# Slave.net
KiCad netlist of a schematic drawn in EAGLE
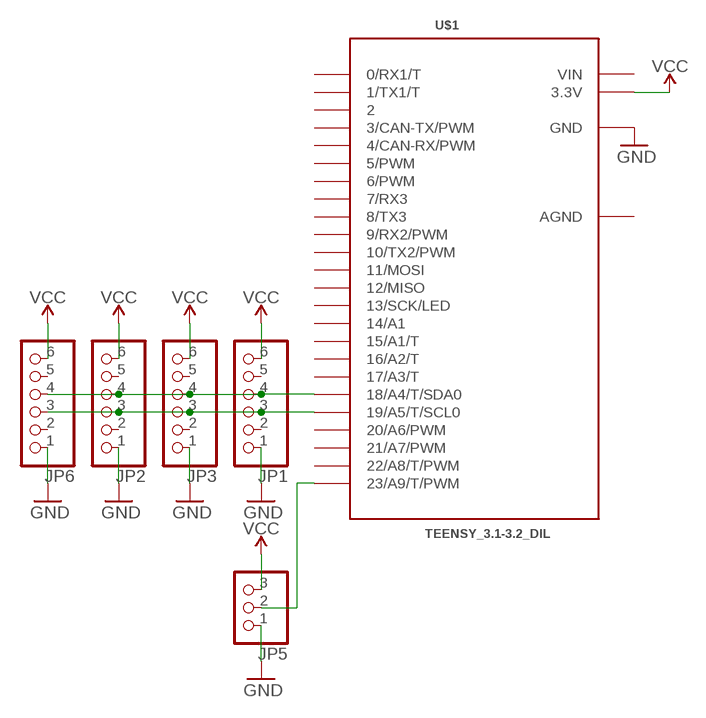
[diagram p0: schematic, sheet 1]

(export (version "E")
  (design (tool "Eeschema 10.0.6"))
  (components
    (comp (ref "JP1")
      (value "PINHD-1X6")
      (footprint "eagle-import:1X06")
      (libsource (lib "eagle-import") (part "PINHD-1X6"))
    )
    (comp (ref "JP2")
      (value "PINHD-1X6/90")
      (footprint "eagle-import:1X06_90")
      (libsource (lib "eagle-import") (part "PINHD-1X6/90"))
    )
    (comp (ref "JP3")
      (value "PINHD-1X6/90")
      (footprint "eagle-import:1X06_90")
      (libsource (lib "eagle-import") (part "PINHD-1X6/90"))
    )
    (comp (ref "JP5")
      (value "PINHD-1X3")
      (footprint "eagle-import:1X03")
      (libsource (lib "eagle-import") (part "PINHD-1X3"))
    )
    (comp (ref "JP6")
      (value "PINHD-1X6/90")
      (footprint "eagle-import:1X06_90")
      (libsource (lib "eagle-import") (part "PINHD-1X6/90"))
    )
    (comp (ref "U$1")
      (value "TEENSY_3.1-3.2_DIL")
      (footprint "eagle-import:TEENSY_3.0-3.2&LC_DIL")
      (libsource (lib "eagle-import") (part "TEENSY_3.1-3.2_DIL"))
    )
  )
  (nets
    (net (code "1") (name "/AGND") (class "Default")
      (node (ref "U$1") (pin "AGND") (pinfunction "AGND_AGND") (pintype "power_in"))
    )
    (net (code "2") (name "/VIN") (class "Default")
      (node (ref "U$1") (pin "VIN") (pinfunction "VIN_VIN") (pintype "power_in"))
    )
    (net (code "3") (name "GND") (class "Default")
      (node (ref "JP1") (pin "1") (pinfunction "1_1") (pintype "passive"))
      (node (ref "JP2") (pin "1") (pinfunction "1_1") (pintype "passive"))
      (node (ref "JP3") (pin "1") (pinfunction "1_1") (pintype "passive"))
      (node (ref "JP5") (pin "1") (pinfunction "1_1") (pintype "passive"))
      (node (ref "JP6") (pin "1") (pinfunction "1_1") (pintype "passive"))
      (node (ref "U$1") (pin "GND") (pinfunction "GND_GND") (pintype "power_in"))
    )
    (net (code "4") (name "Net-(U$1-18{slash}A4{slash}T{slash}SDA0)") (class "Default")
      (node (ref "JP1") (pin "4") (pinfunction "4_4") (pintype "passive"))
      (node (ref "JP2") (pin "4") (pinfunction "4_4") (pintype "passive"))
      (node (ref "JP3") (pin "4") (pinfunction "4_4") (pintype "passive"))
      (node (ref "JP6") (pin "4") (pinfunction "4_4") (pintype "passive"))
      (node (ref "U$1") (pin "18/A4") (pinfunction "18/A4/T/SDA0_18/A4") (pintype "bidirectional"))
    )
    (net (code "5") (name "Net-(U$1-19{slash}A5{slash}T{slash}SCL0)") (class "Default")
      (node (ref "JP1") (pin "3") (pinfunction "3_3") (pintype "passive"))
      (node (ref "JP2") (pin "3") (pinfunction "3_3") (pintype "passive"))
      (node (ref "JP3") (pin "3") (pinfunction "3_3") (pintype "passive"))
      (node (ref "JP6") (pin "3") (pinfunction "3_3") (pintype "passive"))
      (node (ref "U$1") (pin "19/A5") (pinfunction "19/A5/T/SCL0_19/A5") (pintype "bidirectional"))
    )
    (net (code "6") (name "Net-(U$1-23{slash}A9{slash}T{slash}PWM)") (class "Default")
      (node (ref "JP5") (pin "2") (pinfunction "2_2") (pintype "passive"))
      (node (ref "U$1") (pin "23/A9") (pinfunction "23/A9/T/PWM_23/A9") (pintype "bidirectional"))
    )
    (net (code "7") (name "VCC") (class "Default")
      (node (ref "JP1") (pin "6") (pinfunction "6_6") (pintype "passive"))
      (node (ref "JP2") (pin "6") (pinfunction "6_6") (pintype "passive"))
      (node (ref "JP3") (pin "6") (pinfunction "6_6") (pintype "passive"))
      (node (ref "JP5") (pin "3") (pinfunction "3_3") (pintype "passive"))
      (node (ref "JP6") (pin "6") (pinfunction "6_6") (pintype "passive"))
      (node (ref "U$1") (pin "3.3V") (pinfunction "3.3V_3.3V") (pintype "power_in"))
    )
    (net (code "8") (name "unconnected-(JP1-Pad2)") (class "Default")
      (node (ref "JP1") (pin "2") (pinfunction "2_2") (pintype "passive"))
    )
    (net (code "9") (name "unconnected-(JP1-Pad5)") (class "Default")
      (node (ref "JP1") (pin "5") (pinfunction "5_5") (pintype "passive"))
    )
    (net (code "10") (name "unconnected-(JP2-Pad2)") (class "Default")
      (node (ref "JP2") (pin "2") (pinfunction "2_2") (pintype "passive"))
    )
    (net (code "11") (name "unconnected-(JP2-Pad5)") (class "Default")
      (node (ref "JP2") (pin "5") (pinfunction "5_5") (pintype "passive"))
    )
    (net (code "12") (name "unconnected-(JP3-Pad2)") (class "Default")
      (node (ref "JP3") (pin "2") (pinfunction "2_2") (pintype "passive"))
    )
    (net (code "13") (name "unconnected-(JP3-Pad5)") (class "Default")
      (node (ref "JP3") (pin "5") (pinfunction "5_5") (pintype "passive"))
    )
    (net (code "14") (name "unconnected-(JP6-Pad2)") (class "Default")
      (node (ref "JP6") (pin "2") (pinfunction "2_2") (pintype "passive"))
    )
    (net (code "15") (name "unconnected-(JP6-Pad5)") (class "Default")
      (node (ref "JP6") (pin "5") (pinfunction "5_5") (pintype "passive"))
    )
    (net (code "16") (name "unconnected-(U$1-0{slash}RX1{slash}T-Pad0)") (class "Default")
      (node (ref "U$1") (pin "0") (pinfunction "0/RX1/T_0") (pintype "bidirectional"))
    )
    (net (code "17") (name "unconnected-(U$1-1{slash}TX1{slash}T-Pad1)") (class "Default")
      (node (ref "U$1") (pin "1") (pinfunction "1/TX1/T_1") (pintype "bidirectional"))
    )
    (net (code "18") (name "unconnected-(U$1-3{slash}CAN-TX{slash}PWM-Pad3)") (class "Default")
      (node (ref "U$1") (pin "3") (pinfunction "3/CAN-TX/PWM_3") (pintype "bidirectional"))
    )
    (net (code "19") (name "unconnected-(U$1-4{slash}CAN-RX{slash}PWM-Pad4)") (class "Default")
      (node (ref "U$1") (pin "4") (pinfunction "4/CAN-RX/PWM_4") (pintype "bidirectional"))
    )
    (net (code "20") (name "unconnected-(U$1-5{slash}PWM-Pad5)") (class "Default")
      (node (ref "U$1") (pin "5") (pinfunction "5/PWM_5") (pintype "bidirectional"))
    )
    (net (code "21") (name "unconnected-(U$1-6{slash}PWM-Pad6)") (class "Default")
      (node (ref "U$1") (pin "6") (pinfunction "6/PWM_6") (pintype "bidirectional"))
    )
    (net (code "22") (name "unconnected-(U$1-7{slash}RX3-Pad7)") (class "Default")
      (node (ref "U$1") (pin "7") (pinfunction "7/RX3_7") (pintype "bidirectional"))
    )
    (net (code "23") (name "unconnected-(U$1-8{slash}TX3-Pad8)") (class "Default")
      (node (ref "U$1") (pin "8") (pinfunction "8/TX3_8") (pintype "bidirectional"))
    )
    (net (code "24") (name "unconnected-(U$1-9{slash}RX2{slash}PWM-Pad9)") (class "Default")
      (node (ref "U$1") (pin "9") (pinfunction "9/RX2/PWM_9") (pintype "bidirectional"))
    )
    (net (code "25") (name "unconnected-(U$1-10{slash}TX2{slash}PWM-Pad10)") (class "Default")
      (node (ref "U$1") (pin "10") (pinfunction "10/TX2/PWM_10") (pintype "bidirectional"))
    )
    (net (code "26") (name "unconnected-(U$1-11{slash}MOSI-Pad11)") (class "Default")
      (node (ref "U$1") (pin "11") (pinfunction "11/MOSI_11") (pintype "bidirectional"))
    )
    (net (code "27") (name "unconnected-(U$1-12{slash}MISO-Pad12)") (class "Default")
      (node (ref "U$1") (pin "12") (pinfunction "12/MISO_12") (pintype "bidirectional"))
    )
    (net (code "28") (name "unconnected-(U$1-13{slash}SCK{slash}LED-Pad13)") (class "Default")
      (node (ref "U$1") (pin "13") (pinfunction "13/SCK/LED_13") (pintype "bidirectional"))
    )
    (net (code "29") (name "unconnected-(U$1-14{slash}A1-Pad14{slash}A0)") (class "Default")
      (node (ref "U$1") (pin "14/A0") (pinfunction "14/A1_14/A0") (pintype "bidirectional"))
    )
    (net (code "30") (name "unconnected-(U$1-15{slash}A1{slash}T-Pad15{slash}A1)") (class "Default")
      (node (ref "U$1") (pin "15/A1") (pinfunction "15/A1/T_15/A1") (pintype "bidirectional"))
    )
    (net (code "31") (name "unconnected-(U$1-16{slash}A2{slash}T-Pad16{slash}A2)") (class "Default")
      (node (ref "U$1") (pin "16/A2") (pinfunction "16/A2/T_16/A2") (pintype "bidirectional"))
    )
    (net (code "32") (name "unconnected-(U$1-17{slash}A3{slash}T-Pad17{slash}A3)") (class "Default")
      (node (ref "U$1") (pin "17/A3") (pinfunction "17/A3/T_17/A3") (pintype "bidirectional"))
    )
    (net (code "33") (name "unconnected-(U$1-20{slash}A6{slash}PWM-Pad20{slash}A6)") (class "Default")
      (node (ref "U$1") (pin "20/A6") (pinfunction "20/A6/PWM_20/A6") (pintype "bidirectional"))
    )
    (net (code "34") (name "unconnected-(U$1-21{slash}A7{slash}PWM-Pad21{slash}A7)") (class "Default")
      (node (ref "U$1") (pin "21/A7") (pinfunction "21/A7/PWM_21/A7") (pintype "bidirectional"))
    )
    (net (code "35") (name "unconnected-(U$1-22{slash}A8{slash}T{slash}PWM-Pad22{slash}A8)") (class "Default")
      (node (ref "U$1") (pin "22/A8") (pinfunction "22/A8/T/PWM_22/A8") (pintype "bidirectional"))
    )
    (net (code "36") (name "unconnected-(U$1-Pad2)") (class "Default")
      (node (ref "U$1") (pin "2") (pinfunction "2_2") (pintype "bidirectional"))
    )
  )
)
